# PSU.net
KiCad netlist of a schematic drawn in Altium Designer
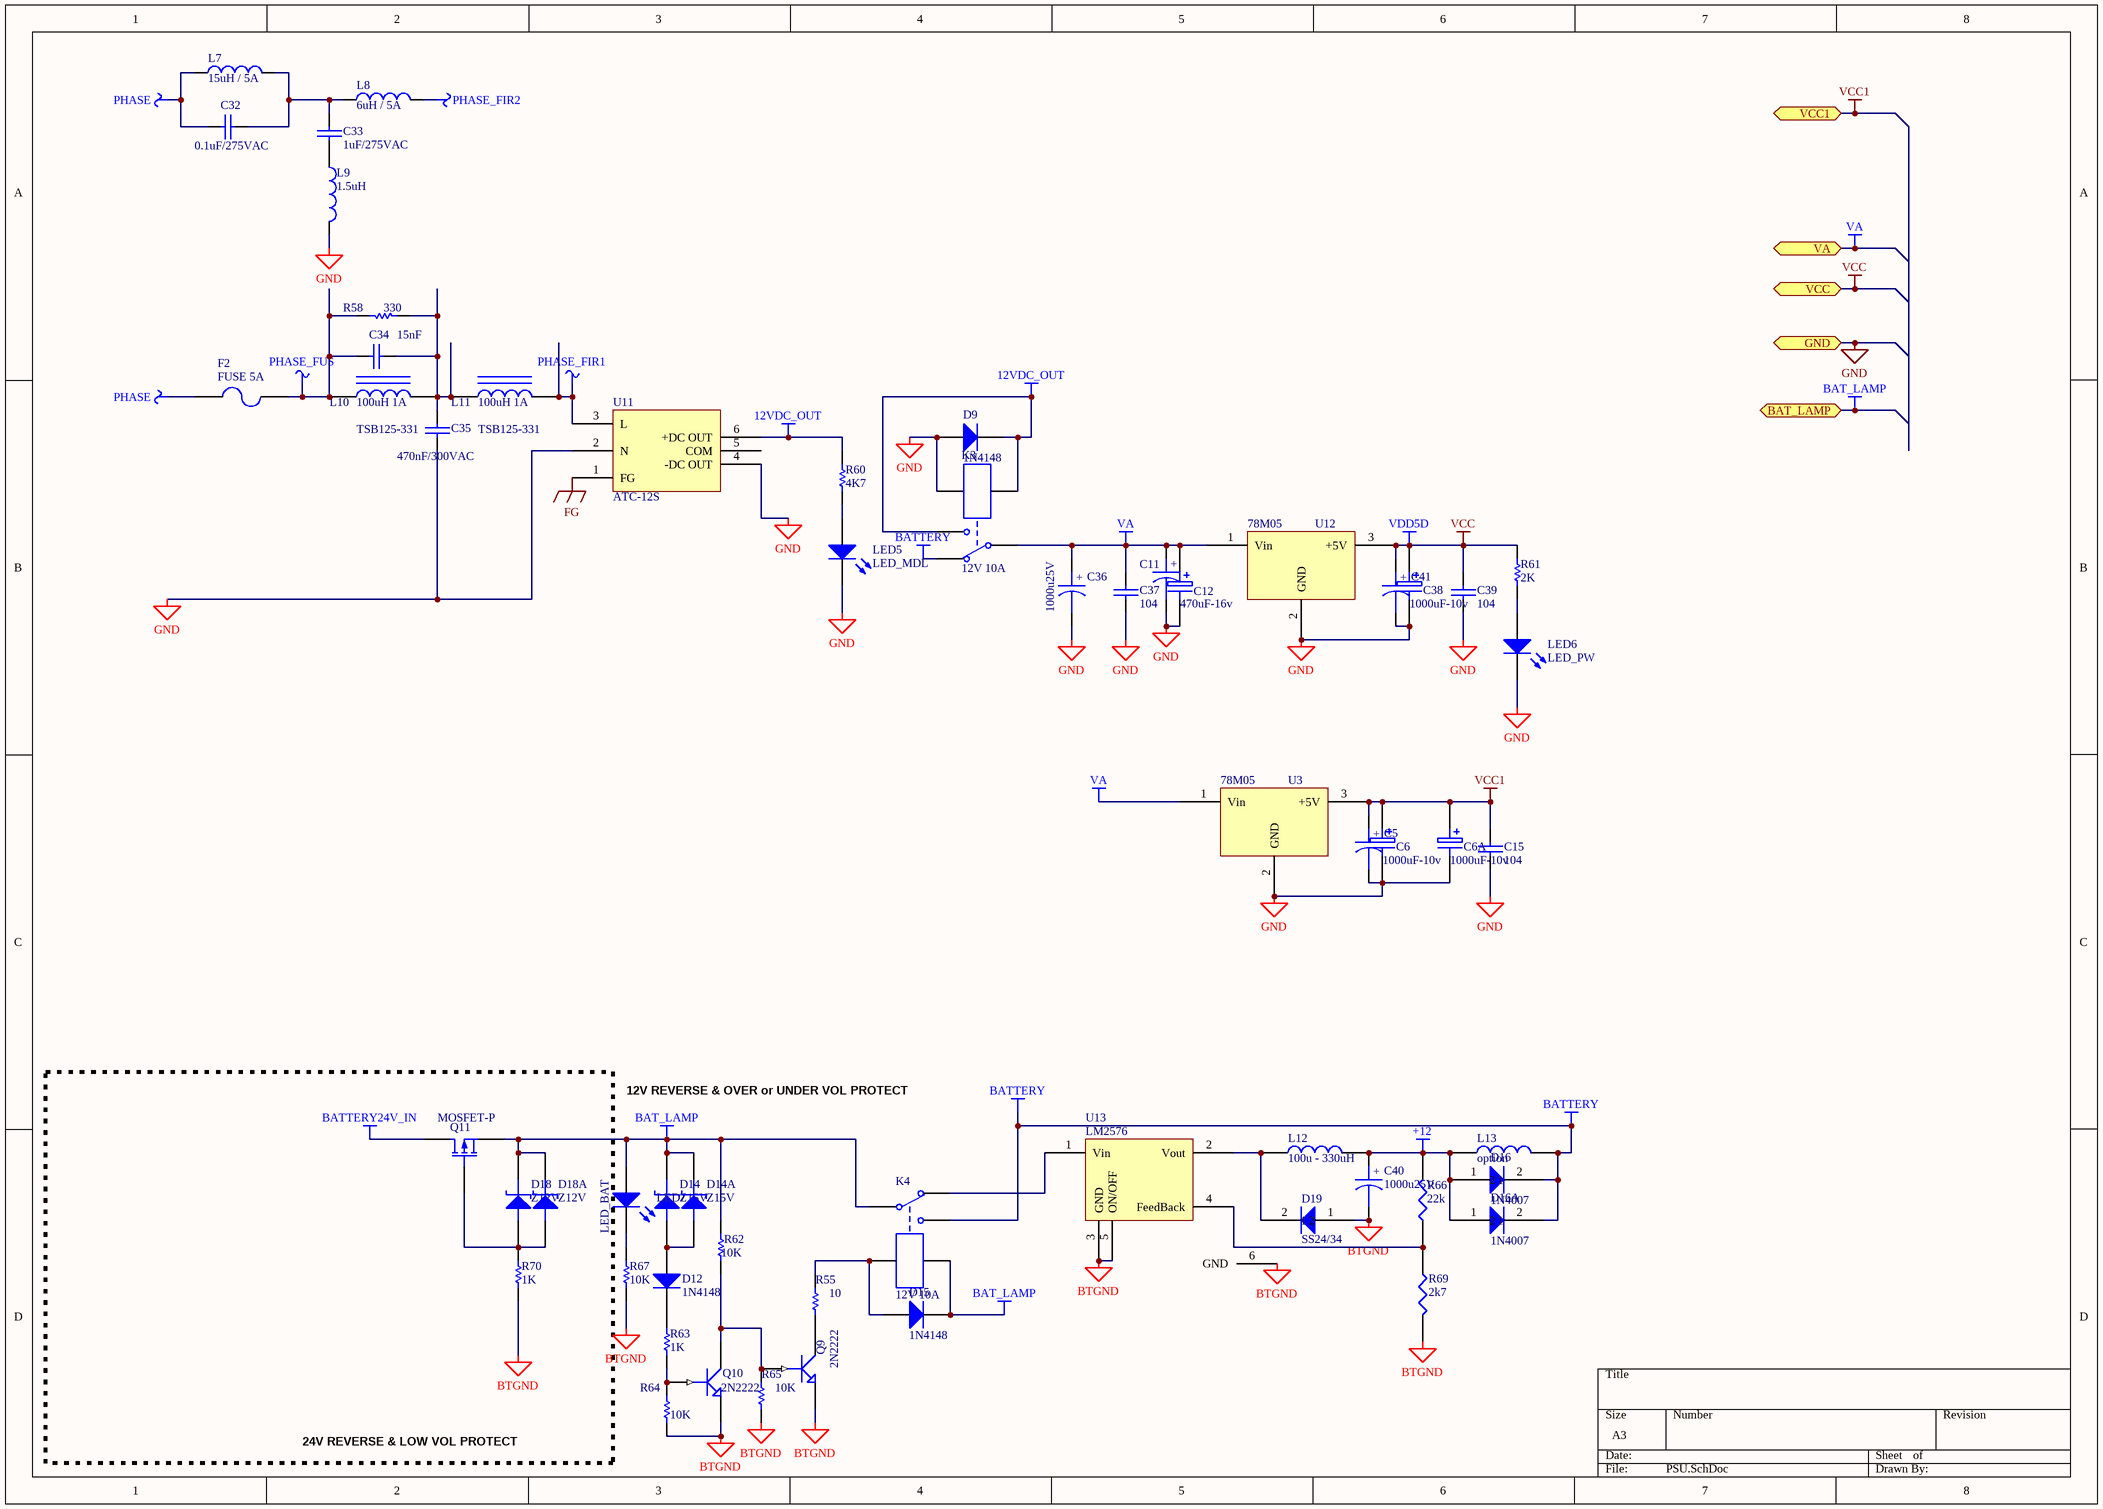
[diagram p0: PSU.SchDoc]

(export (version "E")
  (design (tool "Eeschema 10.0.6"))
  (components
    (comp (ref "C5")
      (value "1000u25V")
      (footprint "CAP40x20")
      (description "Capacitor")
      (libsource (lib "*") (part "CAPACITOR POL"))
    )
    (comp (ref "C6")
      (value "1000uF-10v")
      (footprint "CAP_ELEC_SIZE_E")
      (description "Electrolytic Capacitor")
      (libsource (lib "*") (part "ELECTRO1"))
    )
    (comp (ref "C6A")
      (value "1000uF-10v")
      (footprint "CAP_ELEC_SIZE_E")
      (description "Electrolytic Capacitor")
      (libsource (lib "*") (part "ELECTRO1"))
    )
    (comp (ref "C11")
      (value "1000u25V")
      (footprint "CAP40x20")
      (description "Capacitor")
      (libsource (lib "*") (part "CAPACITOR POL"))
    )
    (comp (ref "C12")
      (value "470uF-16v")
      (footprint "CAP_ELEC_SIZE_E")
      (description "Electrolytic Capacitor")
      (libsource (lib "*") (part "ELECTRO1"))
    )
    (comp (ref "C15")
      (value "104")
      (footprint "C6-0805_N")
      (description "Capacitor")
      (libsource (lib "*") (part "CAP"))
    )
    (comp (ref "C32")
      (value "0.1uF/275VAC")
      (footprint "100n400v")
      (description "0.1uF/275VAC X2")
      (libsource (lib "*") (part "CAP"))
    )
    (comp (ref "C33")
      (value "1uF/275VAC")
      (footprint "CAP1.2/0.5")
      (description "1uF/275VAC X2")
      (libsource (lib "*") (part "CAP"))
    )
    (comp (ref "C34")
      (value "15nF")
      (footprint "R3216[1206]")
      (description "Capacitor")
      (libsource (lib "*") (part "CAP"))
    )
    (comp (ref "C35")
      (value "470nF/300VAC")
      (footprint "100n400v")
      (description "Capacitor")
      (libsource (lib "*") (part "CAP"))
    )
    (comp (ref "C36")
      (value "1000u25V")
      (footprint "CAP40x20")
      (description "Capacitor")
      (libsource (lib "*") (part "CAPACITOR POL"))
    )
    (comp (ref "C37")
      (value "104")
      (footprint "C6-0805_N")
      (description "Capacitor")
      (libsource (lib "*") (part "CAP"))
    )
    (comp (ref "C38")
      (value "1000uF-10v")
      (footprint "CAP_ELEC_SIZE_E")
      (description "Electrolytic Capacitor")
      (libsource (lib "*") (part "ELECTRO1"))
    )
    (comp (ref "C39")
      (value "104")
      (footprint "C6-0805_N")
      (description "Capacitor")
      (libsource (lib "*") (part "CAP"))
    )
    (comp (ref "C40")
      (value "1000u25V")
      (footprint "CAP40x20")
      (description "Capacitor")
      (libsource (lib "*") (part "CAPACITOR POL"))
    )
    (comp (ref "C41")
      (value "1000u25V")
      (footprint "CAP40x20")
      (description "Capacitor")
      (libsource (lib "*") (part "CAPACITOR POL"))
    )
    (comp (ref "D9")
      (value "1N4148")
      (footprint "SOD80, LL-34")
      (description "1 Amp General Purpose Rectifier")
      (fields (field (name "PUBLISHER") "Altium Limited"))
      (libsource (lib "*") (part "Diode 1N4007"))
    )
    (comp (ref "D12")
      (value "1N4148")
      (footprint "SOD80, LL-34")
      (description "1 Amp General Purpose Rectifier")
      (fields (field (name "PUBLISHER") "Altium Limited"))
      (libsource (lib "*") (part "Diode 1N4007"))
    )
    (comp (ref "D14")
      (value "Z15V")
      (footprint "DO-35")
      (description "Zener Diode")
      (libsource (lib "*") (part "ZENER2"))
    )
    (comp (ref "D14A")
      (value "Z15V")
      (footprint "SOT23-3")
      (description "Zener Diode")
      (libsource (lib "*") (part "ZENER2"))
    )
    (comp (ref "D15")
      (value "1N4148")
      (footprint "SOD80, LL-34")
      (description "1 Amp General Purpose Rectifier")
      (fields (field (name "PUBLISHER") "Altium Limited"))
      (libsource (lib "*") (part "Diode 1N4007"))
    )
    (comp (ref "D16")
      (value "1N4007")
      (footprint "DO-214AA")
      (description "Hoangphat")
      (libsource (lib "*") (part "DIODE"))
    )
    (comp (ref "D16A")
      (value "1N4007")
      (footprint "DO-214AA")
      (description "Hoangphat")
      (libsource (lib "*") (part "DIODE"))
    )
    (comp (ref "D18")
      (value "Z12V")
      (footprint "DO-35")
      (description "Zener Diode")
      (libsource (lib "*") (part "ZENER2"))
    )
    (comp (ref "D18A")
      (value "Z12V")
      (footprint "SOD80, LL-34")
      (description "Zener Diode")
      (libsource (lib "*") (part "ZENER2"))
    )
    (comp (ref "D19")
      (value "SS24/34")
      (footprint "DO-214AA")
      (description "Hoangphat")
      (libsource (lib "*") (part "DIODE"))
    )
    (comp (ref "F2")
      (value "FUSE 5A")
      (footprint "FUSE2")
      (description "Fuse")
      (libsource (lib "*") (part "FUSE2"))
    )
    (comp (ref "K3")
      (value "12V 10A")
      (footprint "RELAYVUONG")
      (description "G5LA-10A/250VAC / SRC-12VDC-SL-C")
      (fields (field (name "PUBLISHER") "Altium Limited"))
      (libsource (lib "Miscellaneous Devices") (part "Relay-SPDT"))
    )
    (comp (ref "K4")
      (value "12V 10A")
      (footprint "RELAYVUONG")
      (description "G5LA-10A/250VAC / SRC-12VDC-SL-C")
      (fields (field (name "PUBLISHER") "Altium Limited"))
      (libsource (lib "Miscellaneous Devices") (part "Relay-SPDT"))
    )
    (comp (ref "L7")
      (value "15uH / 5A")
      (footprint "IND26x8")
      (description "Inductor")
      (fields (field (name "PUBLISHER") "Altium Limited"))
      (libsource (lib "Miscellaneous Devices") (part "Inductor"))
    )
    (comp (ref "L8")
      (value "6uH / 5A")
      (footprint "IND15X7")
      (description "Inductor")
      (fields (field (name "PUBLISHER") "Altium Limited"))
      (libsource (lib "Miscellaneous Devices") (part "Inductor"))
    )
    (comp (ref "L9")
      (value "1.5uH")
      (footprint "IND15x7")
      (description "Inductor")
      (fields (field (name "PUBLISHER") "Altium Limited"))
      (libsource (lib "Miscellaneous Devices") (part "Inductor"))
    )
    (comp (ref "L10")
      (value "100uH 1A")
      (footprint "IND1207")
      (description "100uH 1A SMD HP")
      (fields (field (name "ALTIUM_VALUE") "TSB125-331"))
      (libsource (lib "*") (part "INDUCTOR IRON"))
    )
    (comp (ref "L11")
      (value "100uH 1A")
      (footprint "IND1207")
      (description "100uH 1A SMD HP")
      (fields (field (name "ALTIUM_VALUE") "TSB125-331"))
      (libsource (lib "*") (part "INDUCTOR IRON"))
    )
    (comp (ref "L12") (value "100u - 330uH") (footprint "IND1207") (libsource (lib "*") (part "INDUCTOR")))
    (comp (ref "L13") (value "option") (footprint "axial-0.3") (libsource (lib "*") (part "INDUCTOR")))
    (comp (ref "LED5")
      (value "LED_MDL")
      (footprint "LED3mm")
      (description "Typical BLUE SiC LED")
      (fields (field (name "PUBLISHER") "Altium Limited"))
      (libsource (lib "Miscellaneous Devices") (part "LED3"))
    )
    (comp (ref "LED6")
      (value "LED_PW")
      (footprint "LED3mm")
      (description "Typical BLUE SiC LED")
      (fields (field (name "PUBLISHER") "Altium Limited"))
      (libsource (lib "Miscellaneous Devices") (part "LED3"))
    )
    (comp (ref "LED7")
      (value "LED_BAT")
      (footprint "LED3mm")
      (description "Typical BLUE SiC LED")
      (fields (field (name "PUBLISHER") "Altium Limited"))
      (libsource (lib "Miscellaneous Devices") (part "LED3"))
    )
    (comp (ref "Q9")
      (value "2N2222")
      (footprint "SOT23-3")
      (description "NPN Transistor")
      (libsource (lib "*") (part "NPN1"))
    )
    (comp (ref "Q10")
      (value "2N2222")
      (footprint "SOT23-3")
      (description "NPN Transistor")
      (libsource (lib "*") (part "NPN1"))
    )
    (comp (ref "Q11")
      (value "MOSFET-P")
      (footprint "D2PAK-3")
      (description "P-Channel MOSFET")
      (fields (field (name "PUBLISHER") "Altium Limited"))
      (libsource (lib "Miscellaneous Devices") (part "MOSFET-P"))
    )
    (comp (ref "R55")
      (value "10")
      (footprint "6-0805_N")
      (description "Semiconductor Resistor")
      (fields (field (name "PUBLISHER") "*"))
      (libsource (lib "*") (part "Res Semi"))
    )
    (comp (ref "R58")
      (value "330")
      (footprint "R3216[1206]")
      (description "Semiconductor Resistor")
      (fields (field (name "PUBLISHER") "Altium Limited"))
      (libsource (lib "*") (part "Res Semi"))
    )
    (comp (ref "R60")
      (value "4K7")
      (footprint "6-0805_N")
      (description "Semiconductor Resistor")
      (fields (field (name "PUBLISHER") "*"))
      (libsource (lib "*") (part "Res Semi"))
    )
    (comp (ref "R61")
      (value "2K")
      (footprint "6-0805_N")
      (description "Semiconductor Resistor")
      (fields (field (name "PUBLISHER") "*"))
      (libsource (lib "*") (part "Res Semi"))
    )
    (comp (ref "R62")
      (value "10K")
      (footprint "6-0805_N")
      (description "Semiconductor Resistor")
      (fields (field (name "PUBLISHER") "*"))
      (libsource (lib "*") (part "Res Semi"))
    )
    (comp (ref "R63")
      (value "1K")
      (footprint "6-0805_N")
      (description "Semiconductor Resistor")
      (fields (field (name "PUBLISHER") "*"))
      (libsource (lib "*") (part "Res Semi"))
    )
    (comp (ref "R64")
      (value "10K")
      (footprint "6-0805_N")
      (description "Semiconductor Resistor")
      (fields (field (name "PUBLISHER") "*"))
      (libsource (lib "*") (part "Res Semi"))
    )
    (comp (ref "R65")
      (value "10K")
      (footprint "6-0805_N")
      (description "Semiconductor Resistor")
      (fields (field (name "PUBLISHER") "*"))
      (libsource (lib "*") (part "Res Semi"))
    )
    (comp (ref "R66") (value "22k") (footprint "6-0805_N") (libsource (lib "*") (part "RES1")))
    (comp (ref "R67")
      (value "10K")
      (footprint "6-0805_N")
      (description "Semiconductor Resistor")
      (fields (field (name "PUBLISHER") "*"))
      (libsource (lib "*") (part "Res Semi"))
    )
    (comp (ref "R69") (value "2k7") (footprint "6-0805_N") (libsource (lib "*") (part "RES1")))
    (comp (ref "R70")
      (value "1K")
      (footprint "6-0805_N")
      (description "Semiconductor Resistor")
      (fields (field (name "PUBLISHER") "*"))
      (libsource (lib "*") (part "Res Semi"))
    )
    (comp (ref "U3") (value "78M05") (footprint "D2PAK-3") (libsource (lib "*") (part "MC7805T")))
    (comp (ref "U11")
      (value "ATC-12S")
      (footprint "ATC MODULE")
      (libsource (lib "Schlib1") (part "Component_1"))
    )
    (comp (ref "U12") (value "78M05") (footprint "D2PAK-3") (libsource (lib "*") (part "MC7805T")))
    (comp (ref "U13") (value "LM2576") (footprint "TO-263-5") (libsource (lib "*") (part "LM2576")))
  )
  (nets
    (net (code "1") (name "+12") (class "Default")
      (node (ref "C40") (pin "1") (pinfunction "1_1") (pintype "passive"))
      (node (ref "D16") (pin "1") (pinfunction "1_1") (pintype "passive"))
      (node (ref "D16A") (pin "1") (pinfunction "1_1") (pintype "passive"))
      (node (ref "L12") (pin "2") (pinfunction "2_2") (pintype "passive"))
      (node (ref "L13") (pin "1") (pinfunction "1_1") (pintype "passive"))
      (node (ref "R66") (pin "2") (pinfunction "2_2") (pintype "passive"))
    )
    (net (code "2") (name "12VDC_OUT") (class "Default")
      (node (ref "D9") (pin "2") (pinfunction "K_2") (pintype "passive"))
      (node (ref "K3") (pin "3") (pinfunction "3_3") (pintype "passive"))
      (node (ref "K3") (pin "4") (pinfunction "4_4") (pintype "passive"))
      (node (ref "R60") (pin "2") (pinfunction "2_2") (pintype "passive"))
      (node (ref "U11") (pin "6") (pinfunction "+DC_OUT_6") (pintype "passive"))
    )
    (net (code "3") (name "BATTERY") (class "Default")
      (node (ref "D16") (pin "2") (pinfunction "2_2") (pintype "passive"))
      (node (ref "D16A") (pin "2") (pinfunction "2_2") (pintype "passive"))
      (node (ref "K3") (pin "2") (pinfunction "2_2") (pintype "passive"))
      (node (ref "K4") (pin "3") (pinfunction "3_3") (pintype "passive"))
      (node (ref "L13") (pin "2") (pinfunction "2_2") (pintype "passive"))
    )
    (net (code "4") (name "BATTERY24V_IN") (class "Default")
      (node (ref "Q11") (pin "2") (pinfunction "D_2") (pintype "passive"))
    )
    (net (code "5") (name "BAT_LAMP") (class "Default")
      (node (ref "D14") (pin "2") (pinfunction "K_2") (pintype "passive"))
      (node (ref "D14A") (pin "2") (pinfunction "K_2") (pintype "passive"))
      (node (ref "D15") (pin "2") (pinfunction "K_2") (pintype "passive"))
      (node (ref "D18") (pin "2") (pinfunction "K_2") (pintype "passive"))
      (node (ref "D18A") (pin "2") (pinfunction "K_2") (pintype "passive"))
      (node (ref "K4") (pin "1") (pinfunction "1_1") (pintype "passive"))
      (node (ref "K4") (pin "5") (pinfunction "5_5") (pintype "passive"))
      (node (ref "LED7") (pin "1") (pinfunction "A_1") (pintype "passive"))
      (node (ref "Q11") (pin "3") (pinfunction "S_3") (pintype "passive"))
      (node (ref "R62") (pin "2") (pinfunction "2_2") (pintype "passive"))
    )
    (net (code "6") (name "BTGND") (class "Default")
      (node (ref "C40") (pin "2") (pinfunction "2_2") (pintype "passive"))
      (node (ref "D19") (pin "1") (pinfunction "1_1") (pintype "passive"))
      (node (ref "Q10") (pin "2") (pinfunction "E_2") (pintype "passive"))
      (node (ref "Q9") (pin "2") (pinfunction "E_2") (pintype "passive"))
      (node (ref "R64") (pin "1") (pinfunction "1_1") (pintype "passive"))
      (node (ref "R65") (pin "1") (pinfunction "1_1") (pintype "passive"))
      (node (ref "R67") (pin "1") (pinfunction "1_1") (pintype "passive"))
      (node (ref "R69") (pin "2") (pinfunction "2_2") (pintype "passive"))
      (node (ref "R70") (pin "1") (pinfunction "1_1") (pintype "passive"))
      (node (ref "U13") (pin "3") (pinfunction "GND_3") (pintype "passive"))
      (node (ref "U13") (pin "5") (pinfunction "ON/OFF_5") (pintype "passive"))
      (node (ref "U13") (pin "6") (pinfunction "GND_6") (pintype "passive"))
    )
    (net (code "7") (name "FG") (class "Default")
      (node (ref "U11") (pin "1") (pinfunction "FG_1") (pintype "passive"))
    )
    (net (code "8") (name "GND") (class "Default")
      (node (ref "C11") (pin "2") (pinfunction "2_2") (pintype "passive"))
      (node (ref "C12") (pin "2") (pinfunction "2_2") (pintype "passive"))
      (node (ref "C15") (pin "2") (pinfunction "2_2") (pintype "passive"))
      (node (ref "C35") (pin "1") (pinfunction "1_1") (pintype "passive"))
      (node (ref "C36") (pin "2") (pinfunction "2_2") (pintype "passive"))
      (node (ref "C37") (pin "2") (pinfunction "2_2") (pintype "passive"))
      (node (ref "C38") (pin "2") (pinfunction "2_2") (pintype "passive"))
      (node (ref "C39") (pin "2") (pinfunction "2_2") (pintype "passive"))
      (node (ref "C41") (pin "2") (pinfunction "2_2") (pintype "passive"))
      (node (ref "C5") (pin "2") (pinfunction "2_2") (pintype "passive"))
      (node (ref "C6") (pin "2") (pinfunction "2_2") (pintype "passive"))
      (node (ref "C6A") (pin "2") (pinfunction "2_2") (pintype "passive"))
      (node (ref "D9") (pin "1") (pinfunction "A_1") (pintype "passive"))
      (node (ref "K3") (pin "5") (pinfunction "5_5") (pintype "passive"))
      (node (ref "L9") (pin "2") (pinfunction "2_2") (pintype "passive"))
      (node (ref "LED5") (pin "2") (pinfunction "K_2") (pintype "passive"))
      (node (ref "LED6") (pin "2") (pinfunction "K_2") (pintype "passive"))
      (node (ref "U11") (pin "2") (pinfunction "N_2") (pintype "passive"))
      (node (ref "U11") (pin "4") (pinfunction "-DC_OUT_4") (pintype "passive"))
      (node (ref "U12") (pin "2") (pinfunction "GND_2") (pintype "passive"))
      (node (ref "U3") (pin "2") (pinfunction "GND_2") (pintype "passive"))
    )
    (net (code "9") (name "Net-(C32-Pad1)") (class "Default")
      (node (ref "C32") (pin "1") (pinfunction "1_1") (pintype "passive"))
      (node (ref "C33") (pin "1") (pinfunction "1_1") (pintype "passive"))
      (node (ref "L7") (pin "2") (pinfunction "2_2") (pintype "passive"))
      (node (ref "L8") (pin "1") (pinfunction "1_1") (pintype "passive"))
    )
    (net (code "10") (name "Net-(C33-Pad2)") (class "Default")
      (node (ref "C33") (pin "2") (pinfunction "2_2") (pintype "passive"))
      (node (ref "L9") (pin "1") (pinfunction "1_1") (pintype "passive"))
    )
    (net (code "11") (name "Net-(C34-Pad2)") (class "Default")
      (node (ref "C34") (pin "2") (pinfunction "2_2") (pintype "passive"))
      (node (ref "C35") (pin "2") (pinfunction "2_2") (pintype "passive"))
      (node (ref "L10") (pin "2") (pinfunction "2_2") (pintype "passive"))
      (node (ref "L11") (pin "1") (pinfunction "1_1") (pintype "passive"))
      (node (ref "R58") (pin "1") (pinfunction "1_1") (pintype "passive"))
    )
    (net (code "12") (name "Net-(D12-A)") (class "Default")
      (node (ref "D12") (pin "1") (pinfunction "A_1") (pintype "passive"))
      (node (ref "D14") (pin "1") (pinfunction "A_1") (pintype "passive"))
      (node (ref "D14A") (pin "1") (pinfunction "A_1") (pintype "passive"))
    )
    (net (code "13") (name "Net-(D12-K)") (class "Default")
      (node (ref "D12") (pin "2") (pinfunction "K_2") (pintype "passive"))
      (node (ref "R63") (pin "2") (pinfunction "2_2") (pintype "passive"))
    )
    (net (code "14") (name "Net-(D15-A)") (class "Default")
      (node (ref "D15") (pin "1") (pinfunction "A_1") (pintype "passive"))
      (node (ref "K4") (pin "4") (pinfunction "4_4") (pintype "passive"))
      (node (ref "R55") (pin "2") (pinfunction "2_2") (pintype "passive"))
    )
    (net (code "15") (name "Net-(D18-A)") (class "Default")
      (node (ref "D18") (pin "1") (pinfunction "A_1") (pintype "passive"))
      (node (ref "D18A") (pin "1") (pinfunction "A_1") (pintype "passive"))
      (node (ref "Q11") (pin "1") (pinfunction "G_1") (pintype "passive"))
      (node (ref "R70") (pin "2") (pinfunction "2_2") (pintype "passive"))
    )
    (net (code "16") (name "Net-(LED5-A)") (class "Default")
      (node (ref "LED5") (pin "1") (pinfunction "A_1") (pintype "passive"))
      (node (ref "R60") (pin "1") (pinfunction "1_1") (pintype "passive"))
    )
    (net (code "17") (name "Net-(LED6-A)") (class "Default")
      (node (ref "LED6") (pin "1") (pinfunction "A_1") (pintype "passive"))
      (node (ref "R61") (pin "1") (pinfunction "1_1") (pintype "passive"))
    )
    (net (code "18") (name "Net-(LED7-K)") (class "Default")
      (node (ref "LED7") (pin "2") (pinfunction "K_2") (pintype "passive"))
      (node (ref "R67") (pin "2") (pinfunction "2_2") (pintype "passive"))
    )
    (net (code "19") (name "Net-(Q9-C)") (class "Default")
      (node (ref "Q9") (pin "3") (pinfunction "C_3") (pintype "passive"))
      (node (ref "R55") (pin "1") (pinfunction "1_1") (pintype "passive"))
    )
    (net (code "20") (name "Net-(Q10-B)") (class "Default")
      (node (ref "Q10") (pin "1") (pinfunction "B_1") (pintype "input"))
      (node (ref "R63") (pin "1") (pinfunction "1_1") (pintype "passive"))
      (node (ref "R64") (pin "2") (pinfunction "2_2") (pintype "passive"))
    )
    (net (code "21") (name "Net-(Q10-C)") (class "Default")
      (node (ref "Q10") (pin "3") (pinfunction "C_3") (pintype "passive"))
      (node (ref "Q9") (pin "1") (pinfunction "B_1") (pintype "input"))
      (node (ref "R62") (pin "1") (pinfunction "1_1") (pintype "passive"))
      (node (ref "R65") (pin "2") (pinfunction "2_2") (pintype "passive"))
    )
    (net (code "22") (name "Net-(U13-FeedBack)") (class "Default")
      (node (ref "R66") (pin "1") (pinfunction "1_1") (pintype "passive"))
      (node (ref "R69") (pin "1") (pinfunction "1_1") (pintype "passive"))
      (node (ref "U13") (pin "4") (pinfunction "FeedBack_4") (pintype "passive"))
    )
    (net (code "23") (name "Net-(U13-Vin)") (class "Default")
      (node (ref "K4") (pin "2") (pinfunction "2_2") (pintype "passive"))
      (node (ref "U13") (pin "1") (pinfunction "Vin_1") (pintype "passive"))
    )
    (net (code "24") (name "Net-(U13-Vout)") (class "Default")
      (node (ref "D19") (pin "2") (pinfunction "2_2") (pintype "passive"))
      (node (ref "L12") (pin "1") (pinfunction "1_1") (pintype "passive"))
      (node (ref "U13") (pin "2") (pinfunction "Vout_2") (pintype "passive"))
    )
    (net (code "25") (name "PHASE") (class "Default")
      (node (ref "C32") (pin "2") (pinfunction "2_2") (pintype "passive"))
      (node (ref "F2") (pin "1") (pinfunction "1_1") (pintype "passive"))
      (node (ref "L7") (pin "1") (pinfunction "1_1") (pintype "passive"))
    )
    (net (code "26") (name "PHASE_FIR1") (class "Default")
      (node (ref "L11") (pin "2") (pinfunction "2_2") (pintype "passive"))
      (node (ref "U11") (pin "3") (pinfunction "L_3") (pintype "passive"))
    )
    (net (code "27") (name "PHASE_FIR2") (class "Default")
      (node (ref "L8") (pin "2") (pinfunction "2_2") (pintype "passive"))
    )
    (net (code "28") (name "PHASE_FUS") (class "Default")
      (node (ref "C34") (pin "1") (pinfunction "1_1") (pintype "passive"))
      (node (ref "F2") (pin "2") (pinfunction "2_2") (pintype "passive"))
      (node (ref "L10") (pin "1") (pinfunction "1_1") (pintype "passive"))
      (node (ref "R58") (pin "2") (pinfunction "2_2") (pintype "passive"))
    )
    (net (code "29") (name "VA") (class "Default")
      (node (ref "C11") (pin "1") (pinfunction "1_1") (pintype "passive"))
      (node (ref "C12") (pin "1") (pinfunction "1_1") (pintype "passive"))
      (node (ref "C36") (pin "1") (pinfunction "1_1") (pintype "passive"))
      (node (ref "C37") (pin "1") (pinfunction "1_1") (pintype "passive"))
      (node (ref "K3") (pin "1") (pinfunction "1_1") (pintype "passive"))
      (node (ref "U12") (pin "1") (pinfunction "Vin_1") (pintype "passive"))
      (node (ref "U3") (pin "1") (pinfunction "Vin_1") (pintype "passive"))
    )
    (net (code "30") (name "VCC") (class "Default")
      (node (ref "C38") (pin "1") (pinfunction "1_1") (pintype "passive"))
      (node (ref "C39") (pin "1") (pinfunction "1_1") (pintype "passive"))
      (node (ref "C41") (pin "1") (pinfunction "1_1") (pintype "passive"))
      (node (ref "R61") (pin "2") (pinfunction "2_2") (pintype "passive"))
      (node (ref "U12") (pin "3") (pinfunction "+5V_3") (pintype "passive"))
    )
    (net (code "31") (name "VCC1") (class "Default")
      (node (ref "C15") (pin "1") (pinfunction "1_1") (pintype "passive"))
      (node (ref "C5") (pin "1") (pinfunction "1_1") (pintype "passive"))
      (node (ref "C6") (pin "1") (pinfunction "1_1") (pintype "passive"))
      (node (ref "C6A") (pin "1") (pinfunction "1_1") (pintype "passive"))
      (node (ref "U3") (pin "3") (pinfunction "+5V_3") (pintype "passive"))
    )
    (net (code "32") (name "unconnected-(U11-COM-Pad5)") (class "Default")
      (node (ref "U11") (pin "5") (pinfunction "COM_5") (pintype "passive"))
    )
  )
)
